# Power_Supply.net
KiCad netlist of a schematic drawn in Altium Designer
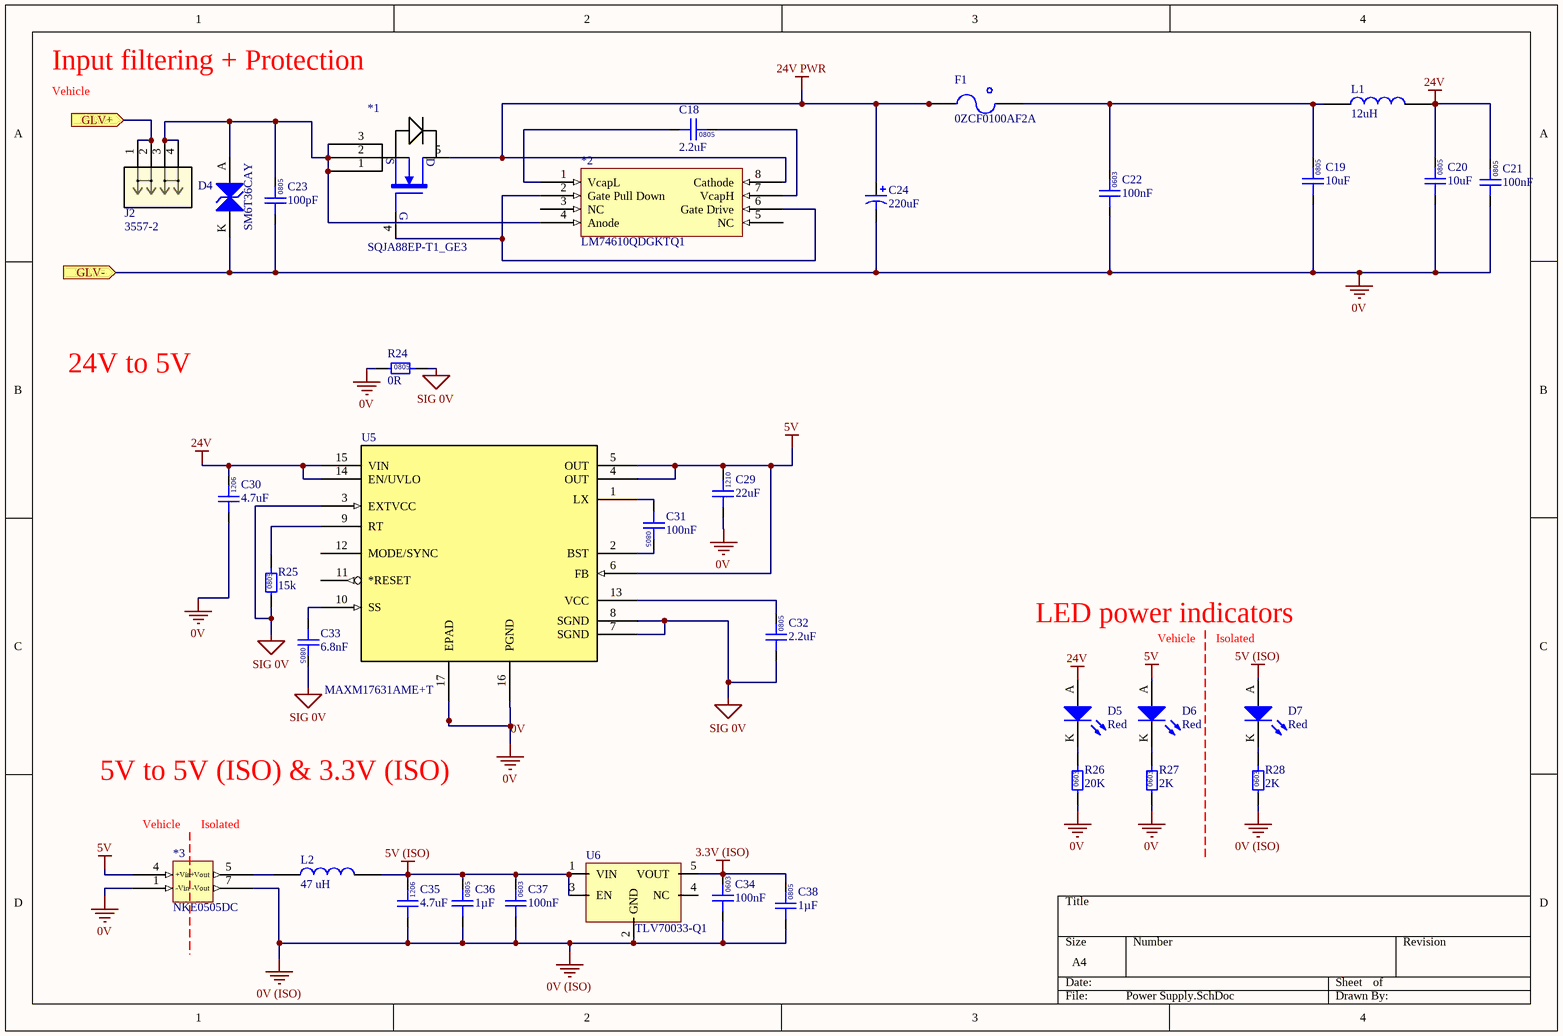
[diagram p0: Power Supply.SchDoc]

(export (version "E")
  (design (tool "Eeschema 10.0.6"))
  (components
    (comp (ref "*1")
      (value "SQJA88EP-T1_GE3")
      (footprint "PowerPak SO-8")
      (description "MOSFET N-CH 40V 30A PPAK SO-8")
      (fields
        (field (name "MANUFACTURER") "Vishay Siliconix")
        (field (name "DIGIKEY PART NUMBER") "742-SQJA88EP-T1_GE3TR-ND")
      )
      (libsource (lib "ts_standard_library") (part "SQJA88EP-T1_GE3"))
    )
    (comp (ref "*2")
      (value "LM74610QDGKTQ1")
      (footprint "SOP65P490X110-8N")
      (description "Hot Swap Voltage Controllers Zero Iq Reverse Polarity Protection")
      (fields (field (name "MANUFACTURER") "Texas Instruments"))
      (libsource (lib "ts_standard_library") (part "LM74610QDGKTQ1"))
    )
    (comp (ref "*3")
      (value "NKE0505DC")
      (footprint "NKE0505DC")
      (description "DC DC CONVERTER 5V 1W")
      (fields
        (field (name "MANUFACTURER") "Murata Power Solutions Inc.")
        (field (name "DIGIKEY PART NUMBER") "811-1433-5-ND")
      )
      (libsource (lib "ts_standard_library") (part "NKE0505DC"))
    )
    (comp (ref "C18")
      (value "2.2uF")
      (footprint "0805")
      (fields
        (field (name "PART NUMBER") "GRM21BR71E225KE11L")
        (field (name "MANUFACTURER") "Murata Electronics")
        (field (name "TOLERANCE") "±10%")
      )
      (libsource (lib "ts_standard_library") (part "Capacitor 0805"))
    )
    (comp (ref "C19")
      (value "10uF")
      (footprint "0805")
      (fields
        (field (name "PART NUMBER") "GRM21BR6YA106KE43L")
        (field (name "MANUFACTURER") "muRata")
        (field (name "TOLERANCE") "10%")
      )
      (libsource (lib "ts_standard_library") (part "Capacitor 0805"))
    )
    (comp (ref "C20")
      (value "10uF")
      (footprint "0805")
      (fields
        (field (name "PART NUMBER") "GRM21BR6YA106KE43L")
        (field (name "MANUFACTURER") "muRata")
        (field (name "TOLERANCE") "10%")
      )
      (libsource (lib "ts_standard_library") (part "Capacitor 0805"))
    )
    (comp (ref "C21")
      (value "100nF")
      (footprint "0805")
      (fields
        (field (name "PART NUMBER") "GCM21BR71H104KA37L")
        (field (name "MANUFACTURER") "muRata")
        (field (name "TOLERANCE") "±10%")
      )
      (libsource (lib "ts_standard_library") (part "Capacitor 0805"))
    )
    (comp (ref "C22")
      (value "100nF")
      (footprint "0603")
      (fields
        (field (name "PART NUMBER") "GCM188L81H104KA57D")
        (field (name "MANUFACTURER") "muRata")
        (field (name "TOLERANCE") "±10%")
      )
      (libsource (lib "ts_standard_library") (part "Capacitor 0603"))
    )
    (comp (ref "C23")
      (value "100pF")
      (footprint "0805")
      (fields
        (field (name "PART NUMBER") "GCM2165C1H101JA16D")
        (field (name "MANUFACTURER") "muRata")
        (field (name "TOLERANCE") "±5%")
      )
      (libsource (lib "ts_standard_library") (part "Capacitor 0805"))
    )
    (comp (ref "C24")
      (value "~")
      (footprint "Vishay Radial 1213")
      (fields
        (field (name "PART NUMBER") "MAL214699106E3")
        (field (name "MANUFACTURER") "Vishay")
        (field (name "TOLERANCE") "20%")
      )
      (libsource (lib "ts_standard_library") (part "Capacitor (Polarised)"))
    )
    (comp (ref "C29")
      (value "22uF")
      (footprint "1210")
      (fields
        (field (name "PART NUMBER") "GRM32ER71E226KE15L")
        (field (name "MANUFACTURER") "Murata Electronics")
        (field (name "TOLERANCE") "±10%")
      )
      (libsource (lib "ts_standard_library") (part "Capacitor 1210"))
    )
    (comp (ref "C30")
      (value "4.7uF")
      (footprint "1206 CAP")
      (fields
        (field (name "PART NUMBER") "GRM31CR71H475KA12K")
        (field (name "MANUFACTURER") "Murata Electronics")
        (field (name "TOLERANCE") "±10%")
      )
      (libsource (lib "ts_standard_library") (part "Capacitor 1206"))
    )
    (comp (ref "C31")
      (value "100nF")
      (footprint "0805")
      (fields
        (field (name "PART NUMBER") "GCM21BR71H104KA37L")
        (field (name "MANUFACTURER") "muRata")
        (field (name "TOLERANCE") "±10%")
      )
      (libsource (lib "ts_standard_library") (part "Capacitor 0805"))
    )
    (comp (ref "C32")
      (value "2.2uF")
      (footprint "0805")
      (fields
        (field (name "PART NUMBER") "GRM21BR71E225KE11L")
        (field (name "MANUFACTURER") "Murata Electronics")
        (field (name "TOLERANCE") "±10%")
      )
      (libsource (lib "ts_standard_library") (part "Capacitor 0805"))
    )
    (comp (ref "C33")
      (value "6.8nF")
      (footprint "0805")
      (fields
        (field (name "PART NUMBER") "GCM2195C1H682JA16D")
        (field (name "MANUFACTURER") "muRata")
        (field (name "TOLERANCE") "±5%")
      )
      (libsource (lib "ts_standard_library") (part "Capacitor 0805"))
    )
    (comp (ref "C34")
      (value "100nF")
      (footprint "0603")
      (fields
        (field (name "PART NUMBER") "GCM188L81H104KA57D")
        (field (name "MANUFACTURER") "muRata")
        (field (name "TOLERANCE") "±10%")
      )
      (libsource (lib "ts_standard_library") (part "Capacitor 0603"))
    )
    (comp (ref "C35")
      (value "4.7uF")
      (footprint "1206 CAP")
      (fields
        (field (name "PART NUMBER") "GRM31CR71H475KA12K")
        (field (name "MANUFACTURER") "Murata Electronics")
        (field (name "TOLERANCE") "±10%")
      )
      (libsource (lib "ts_standard_library") (part "Capacitor 1206"))
    )
    (comp (ref "C36")
      (value "1µF")
      (footprint "0805")
      (fields
        (field (name "PART NUMBER") "GCM21BR71H105KA03L")
        (field (name "MANUFACTURER") "muRata")
        (field (name "TOLERANCE") "±10%")
      )
      (libsource (lib "ts_standard_library") (part "Capacitor 0805"))
    )
    (comp (ref "C37")
      (value "100nF")
      (footprint "0603")
      (fields
        (field (name "PART NUMBER") "GCM188L81H104KA57D")
        (field (name "MANUFACTURER") "muRata")
        (field (name "TOLERANCE") "±10%")
      )
      (libsource (lib "ts_standard_library") (part "Capacitor 0603"))
    )
    (comp (ref "C38")
      (value "1µF")
      (footprint "0805")
      (fields
        (field (name "PART NUMBER") "GCM21BR71H105KA03L")
        (field (name "MANUFACTURER") "muRata")
        (field (name "TOLERANCE") "±10%")
      )
      (libsource (lib "ts_standard_library") (part "Capacitor 0805"))
    )
    (comp (ref "D4")
      (value "SM6T36CAY")
      (footprint "ST SMB DIODE")
      (fields
        (field (name "MANUFACTURER") "STMicroelectronics")
        (field (name "DIGIKEY PART NUMBER") "497-10804-1-ND")
      )
      (libsource (lib "ts_standard_library") (part "TVS (Bidirectional)"))
    )
    (comp (ref "D5")
      (value "Red")
      (footprint "0805 LED")
      (description "Red LED Indication - Discrete 1.75V 0805 (2012 Metric)")
      (fields (field (name "PART NUMBER") "SML-210LTT86") (field (name "MANUFACTURER") "ROHM Semiconductor"))
      (libsource (lib "ts_standard_library") (part "LED"))
    )
    (comp (ref "D6")
      (value "Red")
      (footprint "0805 LED")
      (description "Red LED Indication - Discrete 1.75V 0805 (2012 Metric)")
      (fields (field (name "PART NUMBER") "SML-210LTT86") (field (name "MANUFACTURER") "ROHM Semiconductor"))
      (libsource (lib "ts_standard_library") (part "LED"))
    )
    (comp (ref "D7")
      (value "Red")
      (footprint "0805 LED")
      (description "Red LED Indication - Discrete 1.75V 0805 (2012 Metric)")
      (fields (field (name "PART NUMBER") "SML-210LTT86") (field (name "MANUFACTURER") "ROHM Semiconductor"))
      (libsource (lib "ts_standard_library") (part "LED"))
    )
    (comp (ref "F1")
      (value "0ZCF0100AF2A")
      (footprint "2920")
      (description "PTC RESET FUSE 60V 1A 292")
      (fields
        (field (name "MANUFACTURER") "Littelfuse Inc.")
        (field (name "DIGIKEY PART NUMBER") "507-2070-1-ND")
      )
      (libsource (lib "ts_standard_library") (part "PTC Fuse"))
    )
    (comp (ref "J2")
      (value "3557-2")
      (footprint "35572")
      (description "FUSE BLOCK BLADE 500V 30A PCB")
      (fields
        (field (name "MANUFACTURER") "Keystone Electronics")
        (field (name "DIGIKEY PART NUMBER") "36-3557-2-ND")
        (field (name "COPYRIGHT") "Copyright (C) 2023 Ultra Librarian. All rights reserved.")
      )
      (libsource (lib "ts_standard_library") (part "3557-2"))
    )
    (comp (ref "L1")
      (value "12uH")
      (footprint "1812")
      (fields
        (field (name "PART NUMBER") "RLS-126")
        (field (name "MANUFACTURER") "Recom")
        (field (name "TOLERANCE") "0.2")
      )
      (libsource (lib "ts_standard_library") (part "Inductor"))
    )
    (comp (ref "L2")
      (value "47 uH")
      (footprint "82473C")
      (fields
        (field (name "PART NUMBER") "82473C")
        (field (name "MANUFACTURER") "Murata Power Solutions Inc.")
        (field (name "TOLERANCE") "0.1")
      )
      (libsource (lib "ts_standard_library") (part "Inductor"))
    )
    (comp (ref "R24")
      (value "0R")
      (footprint "0805")
      (fields
        (field (name "PART NUMBER") "RC0805FR070RL")
        (field (name "MANUFACTURER") "YAGEO")
        (field (name "TOLERANCE") "0.01")
      )
      (libsource (lib "ts_standard_library") (part "Resistor 0805"))
    )
    (comp (ref "R25")
      (value "15k")
      (footprint "0805")
      (fields
        (field (name "PART NUMBER") "RC0805FR0715KL")
        (field (name "MANUFACTURER") "YAGEO")
        (field (name "TOLERANCE") "0.01")
      )
      (libsource (lib "ts_standard_library") (part "Resistor 0805"))
    )
    (comp (ref "R26")
      (value "20K")
      (footprint "0603")
      (fields
        (field (name "PART NUMBER") "RC0603FR-0720KL")
        (field (name "MANUFACTURER") "YAGEO")
        (field (name "TOLERANCE") "0.01")
      )
      (libsource (lib "ts_standard_library") (part "Resistor 0603"))
    )
    (comp (ref "R27")
      (value "2K")
      (footprint "0603")
      (fields
        (field (name "PART NUMBER") "RC0603FR-072KL")
        (field (name "MANUFACTURER") "YAGEO")
        (field (name "TOLERANCE") "0.01")
      )
      (libsource (lib "ts_standard_library") (part "Resistor 0603"))
    )
    (comp (ref "R28")
      (value "2K")
      (footprint "0603")
      (fields
        (field (name "PART NUMBER") "RC0603FR-072KL")
        (field (name "MANUFACTURER") "YAGEO")
        (field (name "TOLERANCE") "0.01")
      )
      (libsource (lib "ts_standard_library") (part "Resistor 0603"))
    )
    (comp (ref "U5")
      (value "MAXM17631AME+T")
      (footprint "MAXM17631AME+T")
      (description "DC DC CONVERTER 5V")
      (fields
        (field (name "MANUFACTURER") "Analog Devices")
        (field (name "DIGIKEY PART NUMBER") "175-MAXM17631AME+TTR-ND")
      )
      (libsource (lib "ts_standard_library") (part "MAXM17631AME+T"))
    )
    (comp (ref "U6")
      (value "TLV70033-Q1")
      (footprint "TI SOT-23-5")
      (description "IC REG LINEAR 3.3V 200MA SOT23-5")
      (fields
        (field (name "MANUFACTURER") "Texas Instruments")
        (field (name "DIGIKEY PART NUMBER") "296-27780-1-ND")
      )
      (libsource (lib "ts_standard_library") (part "TLV70033-Q1"))
    )
  )
  (nets
    (net (code "1") (name "/GLV+") (class "Default")
      (node (ref "J2") (pin "1") (pinfunction "1_1") (pintype "passive"))
      (node (ref "J2") (pin "2") (pinfunction "2_2") (pintype "passive"))
    )
    (net (code "2") (name "0V") (class "Default")
      (node (ref "*3") (pin "1") (pinfunction "-Vin_1") (pintype "input"))
      (node (ref "C19") (pin "1") (pinfunction "1_1") (pintype "passive"))
      (node (ref "C20") (pin "1") (pinfunction "1_1") (pintype "passive"))
      (node (ref "C21") (pin "1") (pinfunction "1_1") (pintype "passive"))
      (node (ref "C22") (pin "1") (pinfunction "1_1") (pintype "passive"))
      (node (ref "C23") (pin "1") (pinfunction "1_1") (pintype "passive"))
      (node (ref "C24") (pin "1") (pinfunction "1_1") (pintype "passive"))
      (node (ref "C29") (pin "1") (pinfunction "1_1") (pintype "passive"))
      (node (ref "C30") (pin "1") (pinfunction "1_1") (pintype "passive"))
      (node (ref "D4") (pin "K") (pinfunction "K_K") (pintype "passive"))
      (node (ref "R24") (pin "1") (pinfunction "1_1") (pintype "passive"))
      (node (ref "R26") (pin "1") (pinfunction "1_1") (pintype "passive"))
      (node (ref "R27") (pin "1") (pinfunction "1_1") (pintype "passive"))
      (node (ref "U5") (pin "16") (pinfunction "PGND_16") (pintype "power_in"))
      (node (ref "U5") (pin "17") (pinfunction "EPAD_17") (pintype "power_in"))
    )
    (net (code "3") (name "0V (ISO)") (class "Default")
      (node (ref "*3") (pin "7") (pinfunction "-Vout_7") (pintype "output"))
      (node (ref "C34") (pin "1") (pinfunction "1_1") (pintype "passive"))
      (node (ref "C35") (pin "1") (pinfunction "1_1") (pintype "passive"))
      (node (ref "C36") (pin "1") (pinfunction "1_1") (pintype "passive"))
      (node (ref "C37") (pin "1") (pinfunction "1_1") (pintype "passive"))
      (node (ref "C38") (pin "1") (pinfunction "1_1") (pintype "passive"))
      (node (ref "R28") (pin "1") (pinfunction "1_1") (pintype "passive"))
      (node (ref "U6") (pin "2") (pinfunction "GND_2") (pintype "passive"))
    )
    (net (code "4") (name "3.3V (ISO)") (class "Default")
      (node (ref "C34") (pin "2") (pinfunction "2_2") (pintype "passive"))
      (node (ref "C38") (pin "2") (pinfunction "2_2") (pintype "passive"))
      (node (ref "U6") (pin "5") (pinfunction "VOUT_5") (pintype "passive"))
    )
    (net (code "5") (name "5V") (class "Default")
      (node (ref "*3") (pin "4") (pinfunction "+Vin_4") (pintype "input"))
      (node (ref "C29") (pin "2") (pinfunction "2_2") (pintype "passive"))
      (node (ref "D6") (pin "A") (pinfunction "A_A") (pintype "passive"))
      (node (ref "U5") (pin "4") (pinfunction "OUT_4") (pintype "power_in"))
      (node (ref "U5") (pin "5") (pinfunction "OUT_5") (pintype "power_in"))
      (node (ref "U5") (pin "6") (pinfunction "FB_6") (pintype "input"))
    )
    (net (code "6") (name "5V (ISO)") (class "Default")
      (node (ref "C35") (pin "2") (pinfunction "2_2") (pintype "passive"))
      (node (ref "C36") (pin "2") (pinfunction "2_2") (pintype "passive"))
      (node (ref "C37") (pin "2") (pinfunction "2_2") (pintype "passive"))
      (node (ref "D7") (pin "A") (pinfunction "A_A") (pintype "passive"))
      (node (ref "L2") (pin "1") (pinfunction "1_1") (pintype "passive"))
      (node (ref "U6") (pin "1") (pinfunction "VIN_1") (pintype "passive"))
      (node (ref "U6") (pin "3") (pinfunction "EN_3") (pintype "passive"))
    )
    (net (code "7") (name "24V") (class "Default")
      (node (ref "C20") (pin "2") (pinfunction "2_2") (pintype "passive"))
      (node (ref "C21") (pin "2") (pinfunction "2_2") (pintype "passive"))
      (node (ref "C30") (pin "2") (pinfunction "2_2") (pintype "passive"))
      (node (ref "D5") (pin "A") (pinfunction "A_A") (pintype "passive"))
      (node (ref "L1") (pin "1") (pinfunction "1_1") (pintype "passive"))
      (node (ref "U5") (pin "14") (pinfunction "EN/UVLO_14") (pintype "passive"))
      (node (ref "U5") (pin "15") (pinfunction "VIN_15") (pintype "power_in"))
    )
    (net (code "8") (name "24V PWR") (class "Default")
      (node (ref "*1") (pin "5") (pinfunction "D_5") (pintype "passive"))
      (node (ref "*2") (pin "8") (pinfunction "Cathode_8") (pintype "input"))
      (node (ref "C24") (pin "2") (pinfunction "2_2") (pintype "passive"))
      (node (ref "F1") (pin "1") (pinfunction "1_1") (pintype "passive"))
    )
    (net (code "9") (name "Net-(*1-G)") (class "Default")
      (node (ref "*1") (pin "4") (pinfunction "G_4") (pintype "passive"))
      (node (ref "*2") (pin "2") (pinfunction "Gate_Pull_Down_2") (pintype "input"))
      (node (ref "*2") (pin "6") (pinfunction "Gate_Drive_6") (pintype "input"))
    )
    (net (code "10") (name "Net-(*1-S1)") (class "Default")
      (node (ref "*1") (pin "1") (pinfunction "S1_1") (pintype "passive"))
      (node (ref "*1") (pin "2") (pinfunction "S2_2") (pintype "passive"))
      (node (ref "*1") (pin "3") (pinfunction "S3_3") (pintype "passive"))
      (node (ref "*2") (pin "4") (pinfunction "Anode_4") (pintype "input"))
      (node (ref "C23") (pin "2") (pinfunction "2_2") (pintype "passive"))
      (node (ref "D4") (pin "A") (pinfunction "A_A") (pintype "passive"))
      (node (ref "J2") (pin "3") (pinfunction "3_3") (pintype "passive"))
      (node (ref "J2") (pin "4") (pinfunction "4_4") (pintype "passive"))
    )
    (net (code "11") (name "Net-(*2-VcapH)") (class "Default")
      (node (ref "*2") (pin "7") (pinfunction "VcapH_7") (pintype "input"))
      (node (ref "C18") (pin "2") (pinfunction "2_2") (pintype "passive"))
    )
    (net (code "12") (name "Net-(*2-VcapL)") (class "Default")
      (node (ref "*2") (pin "1") (pinfunction "VcapL_1") (pintype "input"))
      (node (ref "C18") (pin "1") (pinfunction "1_1") (pintype "passive"))
    )
    (net (code "13") (name "Net-(*3-+Vout)") (class "Default")
      (node (ref "*3") (pin "5") (pinfunction "+Vout_5") (pintype "output"))
      (node (ref "L2") (pin "2") (pinfunction "2_2") (pintype "passive"))
    )
    (net (code "14") (name "Net-(C19-Pad2)") (class "Default")
      (node (ref "C19") (pin "2") (pinfunction "2_2") (pintype "passive"))
      (node (ref "C22") (pin "2") (pinfunction "2_2") (pintype "passive"))
      (node (ref "F1") (pin "2") (pinfunction "2_2") (pintype "passive"))
      (node (ref "L1") (pin "2") (pinfunction "2_2") (pintype "passive"))
    )
    (net (code "15") (name "Net-(D5-PadK)") (class "Default")
      (node (ref "D5") (pin "K") (pinfunction "K_K") (pintype "passive"))
      (node (ref "R26") (pin "2") (pinfunction "2_2") (pintype "passive"))
    )
    (net (code "16") (name "Net-(D6-PadK)") (class "Default")
      (node (ref "D6") (pin "K") (pinfunction "K_K") (pintype "passive"))
      (node (ref "R27") (pin "2") (pinfunction "2_2") (pintype "passive"))
    )
    (net (code "17") (name "Net-(D7-PadK)") (class "Default")
      (node (ref "D7") (pin "K") (pinfunction "K_K") (pintype "passive"))
      (node (ref "R28") (pin "2") (pinfunction "2_2") (pintype "passive"))
    )
    (net (code "18") (name "Net-(U5-BST)") (class "Default")
      (node (ref "C31") (pin "2") (pinfunction "2_2") (pintype "passive"))
      (node (ref "U5") (pin "2") (pinfunction "BST_2") (pintype "passive"))
    )
    (net (code "19") (name "Net-(U5-LX)") (class "Default")
      (node (ref "C31") (pin "1") (pinfunction "1_1") (pintype "passive"))
      (node (ref "U5") (pin "1") (pinfunction "LX_1") (pintype "passive"))
    )
    (net (code "20") (name "Net-(U5-RT)") (class "Default")
      (node (ref "R25") (pin "2") (pinfunction "2_2") (pintype "passive"))
      (node (ref "U5") (pin "9") (pinfunction "RT_9") (pintype "passive"))
    )
    (net (code "21") (name "Net-(U5-SS)") (class "Default")
      (node (ref "C33") (pin "1") (pinfunction "1_1") (pintype "passive"))
      (node (ref "U5") (pin "10") (pinfunction "SS_10") (pintype "input"))
    )
    (net (code "22") (name "Net-(U5-VCC)") (class "Default")
      (node (ref "C32") (pin "2") (pinfunction "2_2") (pintype "passive"))
      (node (ref "U5") (pin "13") (pinfunction "VCC_13") (pintype "power_in"))
    )
    (net (code "23") (name "SIG 0V") (class "Default")
      (node (ref "C32") (pin "1") (pinfunction "1_1") (pintype "passive"))
      (node (ref "C33") (pin "2") (pinfunction "2_2") (pintype "passive"))
      (node (ref "R24") (pin "2") (pinfunction "2_2") (pintype "passive"))
      (node (ref "R25") (pin "1") (pinfunction "1_1") (pintype "passive"))
      (node (ref "U5") (pin "3") (pinfunction "EXTVCC_3") (pintype "input"))
      (node (ref "U5") (pin "7") (pinfunction "SGND_7") (pintype "power_in"))
      (node (ref "U5") (pin "8") (pinfunction "SGND_8") (pintype "power_in"))
    )
    (net (code "24") (name "unconnected-(*2-NC-Pad3)") (class "Default")
      (node (ref "*2") (pin "3") (pinfunction "NC_3") (pintype "input"))
    )
    (net (code "25") (name "unconnected-(*2-NC-Pad5)") (class "Default")
      (node (ref "*2") (pin "5") (pinfunction "NC_5") (pintype "input"))
    )
    (net (code "26") (name "unconnected-(U5-*RESET-Pad11)") (class "Default")
      (node (ref "U5") (pin "11") (pinfunction "*RESET_11") (pintype "output"))
    )
    (net (code "27") (name "unconnected-(U5-MODE{slash}SYNC-Pad12)") (class "Default")
      (node (ref "U5") (pin "12") (pinfunction "MODE/SYNC_12") (pintype "passive"))
    )
    (net (code "28") (name "unconnected-(U6-NC-Pad4)") (class "Default")
      (node (ref "U6") (pin "4") (pinfunction "NC_4") (pintype "passive"))
    )
  )
)
